# H22R2x_Frontend_2.net
KiCad netlist of a schematic drawn in Altium Designer
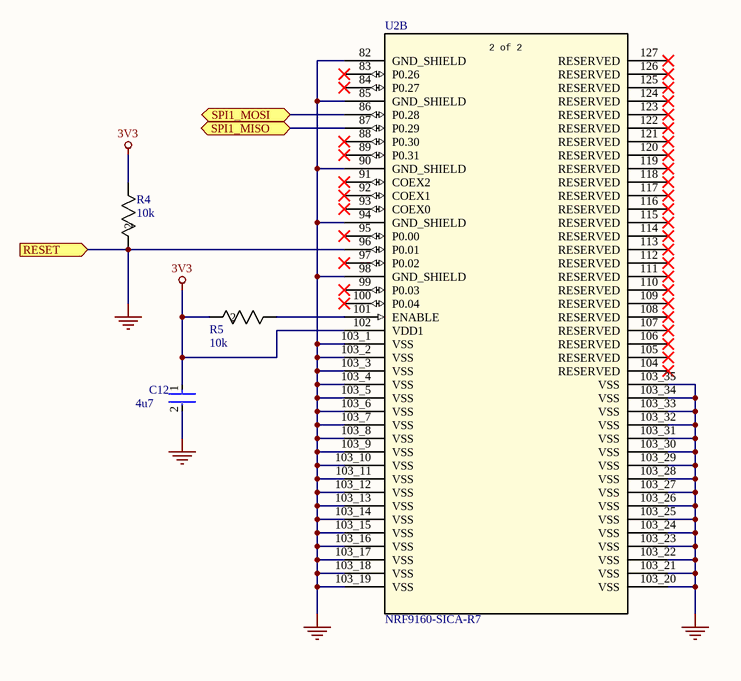
[diagram p0: H22R2x_Frontend 2.SchDoc]

(export (version "E")
  (design (tool "Eeschema 10.0.6"))
  (components
    (comp (ref "C12")
      (value "4u7")
      (footprint "FP-0603-L_1_6_0_15-W_0_8-MFG")
      (description "Ceramic Capacitor General Use 4.7uF ±10% 10V X6S 0603")
      (fields (field (name "TOLERANCE") "10%"))
      (libsource (lib "Altium Content Vault") (part "11868f565c42a9108669ba33697ecf6"))
    )
    (comp (ref "R4")
      (value "10k")
      (footprint "RC0201N_VIS")
      (description "CRCW0201 200 10K 1% ET7 e3")
      (fields
        (field (name "MANUFACTURER_PART_NUMBER") "CRCW020110K0FNED")
        (field (name "COPYRIGHT") "Copyright (C) 2025 Ultra Librarian. All rights reserved.")
      )
      (libsource (lib "Tyme Hopkins") (part "CRCW020110K0FNED"))
    )
    (comp (ref "R5")
      (value "10k")
      (footprint "RC0201N_VIS")
      (description "CRCW0201 200 10K 1% ET7 e3")
      (fields
        (field (name "MANUFACTURER_PART_NUMBER") "CRCW020110K0FNED")
        (field (name "COPYRIGHT") "Copyright (C) 2025 Ultra Librarian. All rights reserved.")
      )
      (libsource (lib "Tyme Hopkins") (part "CRCW020110K0FNED"))
    )
    (comp (ref "U2")
      (value "NRF9160-SICA-R7")
      (footprint "LGA127_16p00X10p50_nRF9160_NOR")
      (description "Description")
      (fields (field (name "COPYRIGHT") "Copyright (C) 2025 Ultra Librarian. All rights reserved."))
      (libsource (lib "Tyme Hopkins") (part "NRF9160-SICA-R7"))
    )
  )
  (nets
    (net (code "1") (name "/SPI1_MISO") (class "Default")
      (node (ref "U2") (pin "87") (pinfunction "P0.29_87") (pintype "bidirectional"))
    )
    (net (code "2") (name "/SPI1_MOSI") (class "Default")
      (node (ref "U2") (pin "86") (pinfunction "P0.28_86") (pintype "bidirectional"))
    )
    (net (code "3") (name "3V3") (class "Default")
      (node (ref "C12") (pin "1") (pinfunction "1_1") (pintype "passive"))
      (node (ref "R4") (pin "1") (pinfunction "1_1") (pintype "passive"))
      (node (ref "R5") (pin "2") (pinfunction "2_2") (pintype "passive"))
      (node (ref "U2") (pin "102") (pinfunction "VDD1_102") (pintype "power_in"))
    )
    (net (code "4") (name "GND") (class "Default")
      (node (ref "C12") (pin "2") (pinfunction "2_2") (pintype "passive"))
      (node (ref "R4") (pin "2") (pinfunction "2_2") (pintype "passive"))
      (node (ref "U2") (pin "103_1") (pinfunction "VSS_103_1") (pintype "power_in"))
      (node (ref "U2") (pin "103_10") (pinfunction "VSS_103_10") (pintype "power_in"))
      (node (ref "U2") (pin "103_11") (pinfunction "VSS_103_11") (pintype "power_in"))
      (node (ref "U2") (pin "103_12") (pinfunction "VSS_103_12") (pintype "power_in"))
      (node (ref "U2") (pin "103_13") (pinfunction "VSS_103_13") (pintype "power_in"))
      (node (ref "U2") (pin "103_14") (pinfunction "VSS_103_14") (pintype "power_in"))
      (node (ref "U2") (pin "103_15") (pinfunction "VSS_103_15") (pintype "power_in"))
      (node (ref "U2") (pin "103_16") (pinfunction "VSS_103_16") (pintype "power_in"))
      (node (ref "U2") (pin "103_17") (pinfunction "VSS_103_17") (pintype "power_in"))
      (node (ref "U2") (pin "103_18") (pinfunction "VSS_103_18") (pintype "power_in"))
      (node (ref "U2") (pin "103_19") (pinfunction "VSS_103_19") (pintype "power_in"))
      (node (ref "U2") (pin "103_2") (pinfunction "VSS_103_2") (pintype "power_in"))
      (node (ref "U2") (pin "103_20") (pinfunction "VSS_103_20") (pintype "power_in"))
      (node (ref "U2") (pin "103_21") (pinfunction "VSS_103_21") (pintype "power_in"))
      (node (ref "U2") (pin "103_22") (pinfunction "VSS_103_22") (pintype "power_in"))
      (node (ref "U2") (pin "103_23") (pinfunction "VSS_103_23") (pintype "power_in"))
      (node (ref "U2") (pin "103_24") (pinfunction "VSS_103_24") (pintype "power_in"))
      (node (ref "U2") (pin "103_25") (pinfunction "VSS_103_25") (pintype "power_in"))
      (node (ref "U2") (pin "103_26") (pinfunction "VSS_103_26") (pintype "power_in"))
      (node (ref "U2") (pin "103_27") (pinfunction "VSS_103_27") (pintype "power_in"))
      (node (ref "U2") (pin "103_28") (pinfunction "VSS_103_28") (pintype "power_in"))
      (node (ref "U2") (pin "103_29") (pinfunction "VSS_103_29") (pintype "power_in"))
      (node (ref "U2") (pin "103_3") (pinfunction "VSS_103_3") (pintype "power_in"))
      (node (ref "U2") (pin "103_30") (pinfunction "VSS_103_30") (pintype "power_in"))
      (node (ref "U2") (pin "103_31") (pinfunction "VSS_103_31") (pintype "power_in"))
      (node (ref "U2") (pin "103_32") (pinfunction "VSS_103_32") (pintype "power_in"))
      (node (ref "U2") (pin "103_33") (pinfunction "VSS_103_33") (pintype "power_in"))
      (node (ref "U2") (pin "103_34") (pinfunction "VSS_103_34") (pintype "power_in"))
      (node (ref "U2") (pin "103_35") (pinfunction "VSS_103_35") (pintype "power_in"))
      (node (ref "U2") (pin "103_4") (pinfunction "VSS_103_4") (pintype "power_in"))
      (node (ref "U2") (pin "103_5") (pinfunction "VSS_103_5") (pintype "power_in"))
      (node (ref "U2") (pin "103_6") (pinfunction "VSS_103_6") (pintype "power_in"))
      (node (ref "U2") (pin "103_7") (pinfunction "VSS_103_7") (pintype "power_in"))
      (node (ref "U2") (pin "103_8") (pinfunction "VSS_103_8") (pintype "power_in"))
      (node (ref "U2") (pin "103_9") (pinfunction "VSS_103_9") (pintype "power_in"))
      (node (ref "U2") (pin "82") (pinfunction "GND_SHIELD_82") (pintype "power_in"))
      (node (ref "U2") (pin "85") (pinfunction "GND_SHIELD_85") (pintype "power_in"))
      (node (ref "U2") (pin "90") (pinfunction "GND_SHIELD_90") (pintype "power_in"))
      (node (ref "U2") (pin "94") (pinfunction "GND_SHIELD_94") (pintype "power_in"))
      (node (ref "U2") (pin "96") (pinfunction "P0.01_96") (pintype "bidirectional"))
      (node (ref "U2") (pin "98") (pinfunction "GND_SHIELD_98") (pintype "power_in"))
    )
    (net (code "5") (name "Net-(U2B-ENABLE)") (class "Default")
      (node (ref "R5") (pin "1") (pinfunction "1_1") (pintype "passive"))
      (node (ref "U2") (pin "101") (pinfunction "ENABLE_101") (pintype "input"))
    )
    (net (code "6") (name "unconnected-(U2B-COEX0-Pad93)") (class "Default")
      (node (ref "U2") (pin "93") (pinfunction "COEX0_93") (pintype "bidirectional+no_connect"))
    )
    (net (code "7") (name "unconnected-(U2B-COEX1-Pad92)") (class "Default")
      (node (ref "U2") (pin "92") (pinfunction "COEX1_92") (pintype "bidirectional+no_connect"))
    )
    (net (code "8") (name "unconnected-(U2B-COEX2-Pad91)") (class "Default")
      (node (ref "U2") (pin "91") (pinfunction "COEX2_91") (pintype "bidirectional+no_connect"))
    )
    (net (code "9") (name "unconnected-(U2B-P0.00-Pad95)") (class "Default")
      (node (ref "U2") (pin "95") (pinfunction "P0.00_95") (pintype "bidirectional+no_connect"))
    )
    (net (code "10") (name "unconnected-(U2B-P0.02-Pad97)") (class "Default")
      (node (ref "U2") (pin "97") (pinfunction "P0.02_97") (pintype "bidirectional+no_connect"))
    )
    (net (code "11") (name "unconnected-(U2B-P0.03-Pad99)") (class "Default")
      (node (ref "U2") (pin "99") (pinfunction "P0.03_99") (pintype "bidirectional+no_connect"))
    )
    (net (code "12") (name "unconnected-(U2B-P0.04-Pad100)") (class "Default")
      (node (ref "U2") (pin "100") (pinfunction "P0.04_100") (pintype "bidirectional+no_connect"))
    )
    (net (code "13") (name "unconnected-(U2B-P0.26-Pad83)") (class "Default")
      (node (ref "U2") (pin "83") (pinfunction "P0.26_83") (pintype "bidirectional+no_connect"))
    )
    (net (code "14") (name "unconnected-(U2B-P0.27-Pad84)") (class "Default")
      (node (ref "U2") (pin "84") (pinfunction "P0.27_84") (pintype "bidirectional+no_connect"))
    )
    (net (code "15") (name "unconnected-(U2B-P0.30-Pad88)") (class "Default")
      (node (ref "U2") (pin "88") (pinfunction "P0.30_88") (pintype "bidirectional+no_connect"))
    )
    (net (code "16") (name "unconnected-(U2B-P0.31-Pad89)") (class "Default")
      (node (ref "U2") (pin "89") (pinfunction "P0.31_89") (pintype "bidirectional+no_connect"))
    )
    (net (code "17") (name "unconnected-(U2B-RESERVED-Pad104)") (class "Default")
      (node (ref "U2") (pin "104") (pinfunction "RESERVED_104") (pintype "passive+no_connect"))
    )
    (net (code "18") (name "unconnected-(U2B-RESERVED-Pad105)") (class "Default")
      (node (ref "U2") (pin "105") (pinfunction "RESERVED_105") (pintype "passive+no_connect"))
    )
    (net (code "19") (name "unconnected-(U2B-RESERVED-Pad106)") (class "Default")
      (node (ref "U2") (pin "106") (pinfunction "RESERVED_106") (pintype "passive+no_connect"))
    )
    (net (code "20") (name "unconnected-(U2B-RESERVED-Pad107)") (class "Default")
      (node (ref "U2") (pin "107") (pinfunction "RESERVED_107") (pintype "passive+no_connect"))
    )
    (net (code "21") (name "unconnected-(U2B-RESERVED-Pad108)") (class "Default")
      (node (ref "U2") (pin "108") (pinfunction "RESERVED_108") (pintype "passive+no_connect"))
    )
    (net (code "22") (name "unconnected-(U2B-RESERVED-Pad109)") (class "Default")
      (node (ref "U2") (pin "109") (pinfunction "RESERVED_109") (pintype "passive+no_connect"))
    )
    (net (code "23") (name "unconnected-(U2B-RESERVED-Pad110)") (class "Default")
      (node (ref "U2") (pin "110") (pinfunction "RESERVED_110") (pintype "passive+no_connect"))
    )
    (net (code "24") (name "unconnected-(U2B-RESERVED-Pad111)") (class "Default")
      (node (ref "U2") (pin "111") (pinfunction "RESERVED_111") (pintype "passive+no_connect"))
    )
    (net (code "25") (name "unconnected-(U2B-RESERVED-Pad112)") (class "Default")
      (node (ref "U2") (pin "112") (pinfunction "RESERVED_112") (pintype "passive+no_connect"))
    )
    (net (code "26") (name "unconnected-(U2B-RESERVED-Pad113)") (class "Default")
      (node (ref "U2") (pin "113") (pinfunction "RESERVED_113") (pintype "passive+no_connect"))
    )
    (net (code "27") (name "unconnected-(U2B-RESERVED-Pad114)") (class "Default")
      (node (ref "U2") (pin "114") (pinfunction "RESERVED_114") (pintype "passive+no_connect"))
    )
    (net (code "28") (name "unconnected-(U2B-RESERVED-Pad115)") (class "Default")
      (node (ref "U2") (pin "115") (pinfunction "RESERVED_115") (pintype "passive+no_connect"))
    )
    (net (code "29") (name "unconnected-(U2B-RESERVED-Pad116)") (class "Default")
      (node (ref "U2") (pin "116") (pinfunction "RESERVED_116") (pintype "passive+no_connect"))
    )
    (net (code "30") (name "unconnected-(U2B-RESERVED-Pad117)") (class "Default")
      (node (ref "U2") (pin "117") (pinfunction "RESERVED_117") (pintype "passive+no_connect"))
    )
    (net (code "31") (name "unconnected-(U2B-RESERVED-Pad118)") (class "Default")
      (node (ref "U2") (pin "118") (pinfunction "RESERVED_118") (pintype "passive+no_connect"))
    )
    (net (code "32") (name "unconnected-(U2B-RESERVED-Pad119)") (class "Default")
      (node (ref "U2") (pin "119") (pinfunction "RESERVED_119") (pintype "passive+no_connect"))
    )
    (net (code "33") (name "unconnected-(U2B-RESERVED-Pad120)") (class "Default")
      (node (ref "U2") (pin "120") (pinfunction "RESERVED_120") (pintype "passive+no_connect"))
    )
    (net (code "34") (name "unconnected-(U2B-RESERVED-Pad121)") (class "Default")
      (node (ref "U2") (pin "121") (pinfunction "RESERVED_121") (pintype "passive+no_connect"))
    )
    (net (code "35") (name "unconnected-(U2B-RESERVED-Pad122)") (class "Default")
      (node (ref "U2") (pin "122") (pinfunction "RESERVED_122") (pintype "passive+no_connect"))
    )
    (net (code "36") (name "unconnected-(U2B-RESERVED-Pad123)") (class "Default")
      (node (ref "U2") (pin "123") (pinfunction "RESERVED_123") (pintype "passive+no_connect"))
    )
    (net (code "37") (name "unconnected-(U2B-RESERVED-Pad124)") (class "Default")
      (node (ref "U2") (pin "124") (pinfunction "RESERVED_124") (pintype "passive+no_connect"))
    )
    (net (code "38") (name "unconnected-(U2B-RESERVED-Pad125)") (class "Default")
      (node (ref "U2") (pin "125") (pinfunction "RESERVED_125") (pintype "passive+no_connect"))
    )
    (net (code "39") (name "unconnected-(U2B-RESERVED-Pad126)") (class "Default")
      (node (ref "U2") (pin "126") (pinfunction "RESERVED_126") (pintype "passive+no_connect"))
    )
    (net (code "40") (name "unconnected-(U2B-RESERVED-Pad127)") (class "Default")
      (node (ref "U2") (pin "127") (pinfunction "RESERVED_127") (pintype "passive+no_connect"))
    )
  )
)
